# DAC_Schematic.net
KiCad netlist of a schematic drawn in Altium Designer
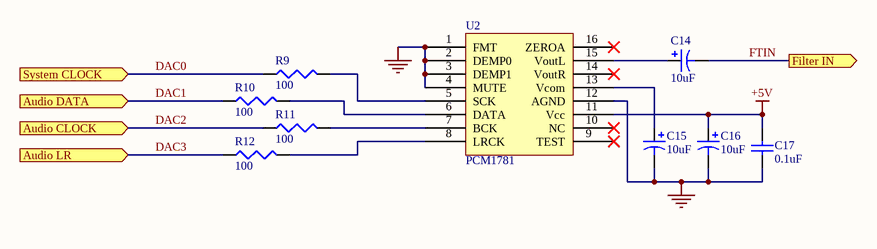
[diagram p0: DAC.Schematic.SchDoc]

(export (version "E")
  (design (tool "Eeschema 10.0.6"))
  (components
    (comp (ref "C14")
      (value "10uF")
      (footprint "RB7.6-15")
      (description "Polarized Capacitor (Radial)")
      (fields (field (name "PUBLISHER") "Altium Limited"))
      (libsource (lib "Miscellaneous Devices") (part "Cap Pol1"))
    )
    (comp (ref "C15")
      (value "10uF")
      (footprint "RB7.6-15")
      (description "Polarized Capacitor (Radial)")
      (fields (field (name "PUBLISHER") "Altium Limited"))
      (libsource (lib "Miscellaneous Devices") (part "Cap Pol1"))
    )
    (comp (ref "C16")
      (value "10uF")
      (footprint "RB7.6-15")
      (description "Polarized Capacitor (Radial)")
      (fields (field (name "PUBLISHER") "Altium Limited"))
      (libsource (lib "Miscellaneous Devices") (part "Cap Pol1"))
    )
    (comp (ref "C17")
      (value "0.1uF")
      (footprint "C1206")
      (description "Capacitor (Semiconductor SIM Model)")
      (fields (field (name "PUBLISHER") "Altium Limited"))
      (libsource (lib "Miscellaneous Devices") (part "Cap Semi"))
    )
    (comp (ref "R9")
      (value "100")
      (footprint "J1-0603")
      (description "Resistor")
      (fields (field (name "PUBLISHER") "Altium Limited"))
      (libsource (lib "Miscellaneous Devices") (part "Res3"))
    )
    (comp (ref "R10")
      (value "100")
      (footprint "J1-0603")
      (description "Resistor")
      (fields (field (name "PUBLISHER") "Altium Limited"))
      (libsource (lib "Miscellaneous Devices") (part "Res3"))
    )
    (comp (ref "R11")
      (value "100")
      (footprint "J1-0603")
      (description "Resistor")
      (fields (field (name "PUBLISHER") "Altium Limited"))
      (libsource (lib "Miscellaneous Devices") (part "Res3"))
    )
    (comp (ref "R12")
      (value "100")
      (footprint "J1-0603")
      (description "Resistor")
      (fields (field (name "PUBLISHER") "Altium Limited"))
      (libsource (lib "Miscellaneous Devices") (part "Res3"))
    )
    (comp (ref "U2")
      (value "PCM1781")
      (footprint "PCM1781")
      (libsource (lib "SynthyTwo.Components") (part "PCM1781 DAC"))
    )
  )
  (nets
    (net (code "1") (name "+5V") (class "Default")
      (node (ref "C16") (pin "1") (pinfunction "1_1") (pintype "passive"))
      (node (ref "C17") (pin "2") (pinfunction "2_2") (pintype "passive"))
      (node (ref "U2") (pin "11") (pinfunction "Vcc_11") (pintype "passive"))
    )
    (net (code "2") (name "/DAC0") (class "Default")
      (node (ref "R9") (pin "1") (pinfunction "1_1") (pintype "passive"))
    )
    (net (code "3") (name "/DAC1") (class "Default")
      (node (ref "R10") (pin "1") (pinfunction "1_1") (pintype "passive"))
    )
    (net (code "4") (name "/DAC2") (class "Default")
      (node (ref "R11") (pin "1") (pinfunction "1_1") (pintype "passive"))
    )
    (net (code "5") (name "/DAC3") (class "Default")
      (node (ref "R12") (pin "1") (pinfunction "1_1") (pintype "passive"))
    )
    (net (code "6") (name "/FTIN") (class "Default")
      (node (ref "C14") (pin "2") (pinfunction "2_2") (pintype "passive"))
    )
    (net (code "7") (name "<NO NET>") (class "Default")
      (node (ref "C15") (pin "2") (pinfunction "2_2") (pintype "passive"))
      (node (ref "C16") (pin "2") (pinfunction "2_2") (pintype "passive"))
      (node (ref "C17") (pin "1") (pinfunction "1_1") (pintype "passive"))
      (node (ref "U2") (pin "1") (pinfunction "FMT_1") (pintype "passive"))
      (node (ref "U2") (pin "12") (pinfunction "AGND_12") (pintype "passive"))
      (node (ref "U2") (pin "2") (pinfunction "DEMP0_2") (pintype "passive"))
      (node (ref "U2") (pin "3") (pinfunction "DEMP1_3") (pintype "passive"))
      (node (ref "U2") (pin "4") (pinfunction "MUTE_4") (pintype "passive"))
    )
    (net (code "8") (name "Net-(U2-BCK)") (class "Default")
      (node (ref "R11") (pin "2") (pinfunction "2_2") (pintype "passive"))
      (node (ref "U2") (pin "7") (pinfunction "BCK_7") (pintype "passive"))
    )
    (net (code "9") (name "Net-(U2-DATA)") (class "Default")
      (node (ref "R10") (pin "2") (pinfunction "2_2") (pintype "passive"))
      (node (ref "U2") (pin "6") (pinfunction "DATA_6") (pintype "passive"))
    )
    (net (code "10") (name "Net-(U2-LRCK)") (class "Default")
      (node (ref "R12") (pin "2") (pinfunction "2_2") (pintype "passive"))
      (node (ref "U2") (pin "8") (pinfunction "LRCK_8") (pintype "passive"))
    )
    (net (code "11") (name "Net-(U2-SCK)") (class "Default")
      (node (ref "R9") (pin "2") (pinfunction "2_2") (pintype "passive"))
      (node (ref "U2") (pin "5") (pinfunction "SCK_5") (pintype "passive"))
    )
    (net (code "12") (name "Net-(U2-Vcom)") (class "Default")
      (node (ref "C15") (pin "1") (pinfunction "1_1") (pintype "passive"))
      (node (ref "U2") (pin "13") (pinfunction "Vcom_13") (pintype "passive"))
    )
    (net (code "13") (name "Net-(U2-VoutL)") (class "Default")
      (node (ref "C14") (pin "1") (pinfunction "1_1") (pintype "passive"))
      (node (ref "U2") (pin "15") (pinfunction "VoutL_15") (pintype "passive"))
    )
    (net (code "14") (name "unconnected-(U2-NC-Pad10)") (class "Default")
      (node (ref "U2") (pin "10") (pinfunction "NC_10") (pintype "passive+no_connect"))
    )
    (net (code "15") (name "unconnected-(U2-TEST-Pad9)") (class "Default")
      (node (ref "U2") (pin "9") (pinfunction "TEST_9") (pintype "passive+no_connect"))
    )
    (net (code "16") (name "unconnected-(U2-VoutR-Pad14)") (class "Default")
      (node (ref "U2") (pin "14") (pinfunction "VoutR_14") (pintype "passive+no_connect"))
    )
    (net (code "17") (name "unconnected-(U2-ZEROA-Pad16)") (class "Default")
      (node (ref "U2") (pin "16") (pinfunction "ZEROA_16") (pintype "passive+no_connect"))
    )
  )
)
